# h_bridge.net
KiCad netlist of a schematic drawn in Altium Designer
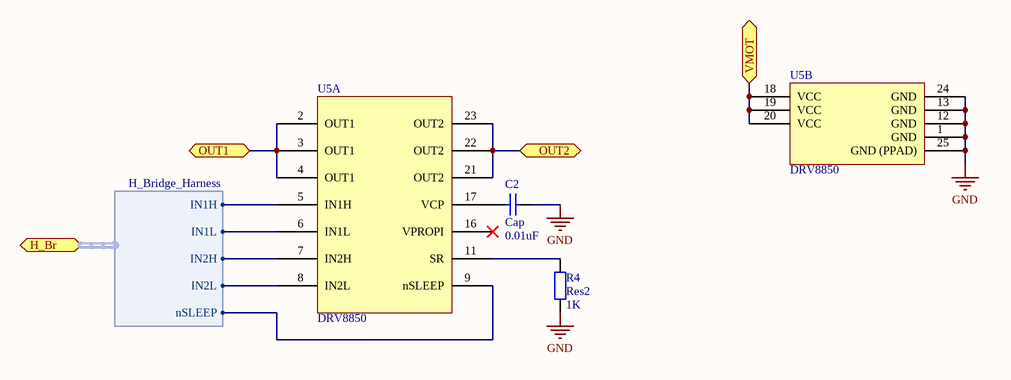
[diagram p0: h_bridge.SchDoc]

(export (version "E")
  (design (tool "Eeschema 10.0.6"))
  (components
    (comp (ref "C2")
      (value "Cap")
      (footprint "RAD-0.3")
      (description "Capacitor")
      (fields (field (name "ALTIUM_VALUE") "0.01uF") (field (name "PUBLISHER") "Altium Limited"))
      (libsource (lib "Miscellaneous Devices") (part "Cap"))
    )
    (comp (ref "R4")
      (value "Res2")
      (footprint "AXIAL-0.4")
      (description "Resistor")
      (fields (field (name "ALTIUM_VALUE") "1K") (field (name "PUBLISHER") "Altium Limited"))
      (libsource (lib "Miscellaneous Devices") (part "Res2"))
    )
    (comp (ref "U5") (value "DRV8850") (libsource (lib "motee_v2") (part "DRV8850")))
  )
  (nets
    (net (code "2") (name "/IN1H") (class "Default")
      (node (ref "U5") (pin "5") (pinfunction "IN1H_5") (pintype "passive"))
    )
    (net (code "3") (name "/IN1L") (class "Default")
      (node (ref "U5") (pin "6") (pinfunction "IN1L_6") (pintype "passive"))
    )
    (net (code "4") (name "/IN2H") (class "Default")
      (node (ref "U5") (pin "7") (pinfunction "IN2H_7") (pintype "passive"))
    )
    (net (code "5") (name "/IN2L") (class "Default")
      (node (ref "U5") (pin "8") (pinfunction "IN2L_8") (pintype "passive"))
    )
    (net (code "6") (name "/OUT1") (class "Default")
      (node (ref "U5") (pin "2") (pinfunction "OUT1_2") (pintype "passive"))
      (node (ref "U5") (pin "3") (pinfunction "OUT1_3") (pintype "passive"))
      (node (ref "U5") (pin "4") (pinfunction "OUT1_4") (pintype "passive"))
    )
    (net (code "7") (name "/OUT2") (class "Default")
      (node (ref "U5") (pin "21") (pinfunction "OUT2_21") (pintype "passive"))
      (node (ref "U5") (pin "22") (pinfunction "OUT2_22") (pintype "passive"))
      (node (ref "U5") (pin "23") (pinfunction "OUT2_23") (pintype "passive"))
    )
    (net (code "8") (name "/VMOT") (class "Default")
      (node (ref "U5") (pin "18") (pinfunction "VCC_18") (pintype "passive"))
      (node (ref "U5") (pin "19") (pinfunction "VCC_19") (pintype "passive"))
      (node (ref "U5") (pin "20") (pinfunction "VCC_20") (pintype "passive"))
    )
    (net (code "9") (name "/nSLEEP") (class "Default")
      (node (ref "U5") (pin "9") (pinfunction "nSLEEP_9") (pintype "passive"))
    )
    (net (code "11") (name "GND") (class "Default")
      (node (ref "C2") (pin "2") (pinfunction "2_2") (pintype "passive"))
      (node (ref "R4") (pin "1") (pinfunction "1_1") (pintype "passive"))
      (node (ref "U5") (pin "1") (pinfunction "GND_1") (pintype "passive"))
      (node (ref "U5") (pin "12") (pinfunction "GND_12") (pintype "passive"))
      (node (ref "U5") (pin "13") (pinfunction "GND_13") (pintype "passive"))
      (node (ref "U5") (pin "24") (pinfunction "GND_24") (pintype "passive"))
      (node (ref "U5") (pin "25") (pinfunction "GND_(PPAD)_25") (pintype "passive"))
    )
    (net (code "12") (name "Net-(U5A-SR)") (class "Default")
      (node (ref "R4") (pin "2") (pinfunction "2_2") (pintype "passive"))
      (node (ref "U5") (pin "11") (pinfunction "SR_11") (pintype "passive"))
    )
    (net (code "13") (name "Net-(U5A-VCP)") (class "Default")
      (node (ref "C2") (pin "1") (pinfunction "1_1") (pintype "passive"))
      (node (ref "U5") (pin "17") (pinfunction "VCP_17") (pintype "passive"))
    )
    (net (code "14") (name "unconnected-(U5A-VPROPI-Pad16)") (class "Default")
      (node (ref "U5") (pin "16") (pinfunction "VPROPI_16") (pintype "passive+no_connect"))
    )
  )
)
